# SIGNAL.net
KiCad netlist of a schematic drawn in Altium Designer
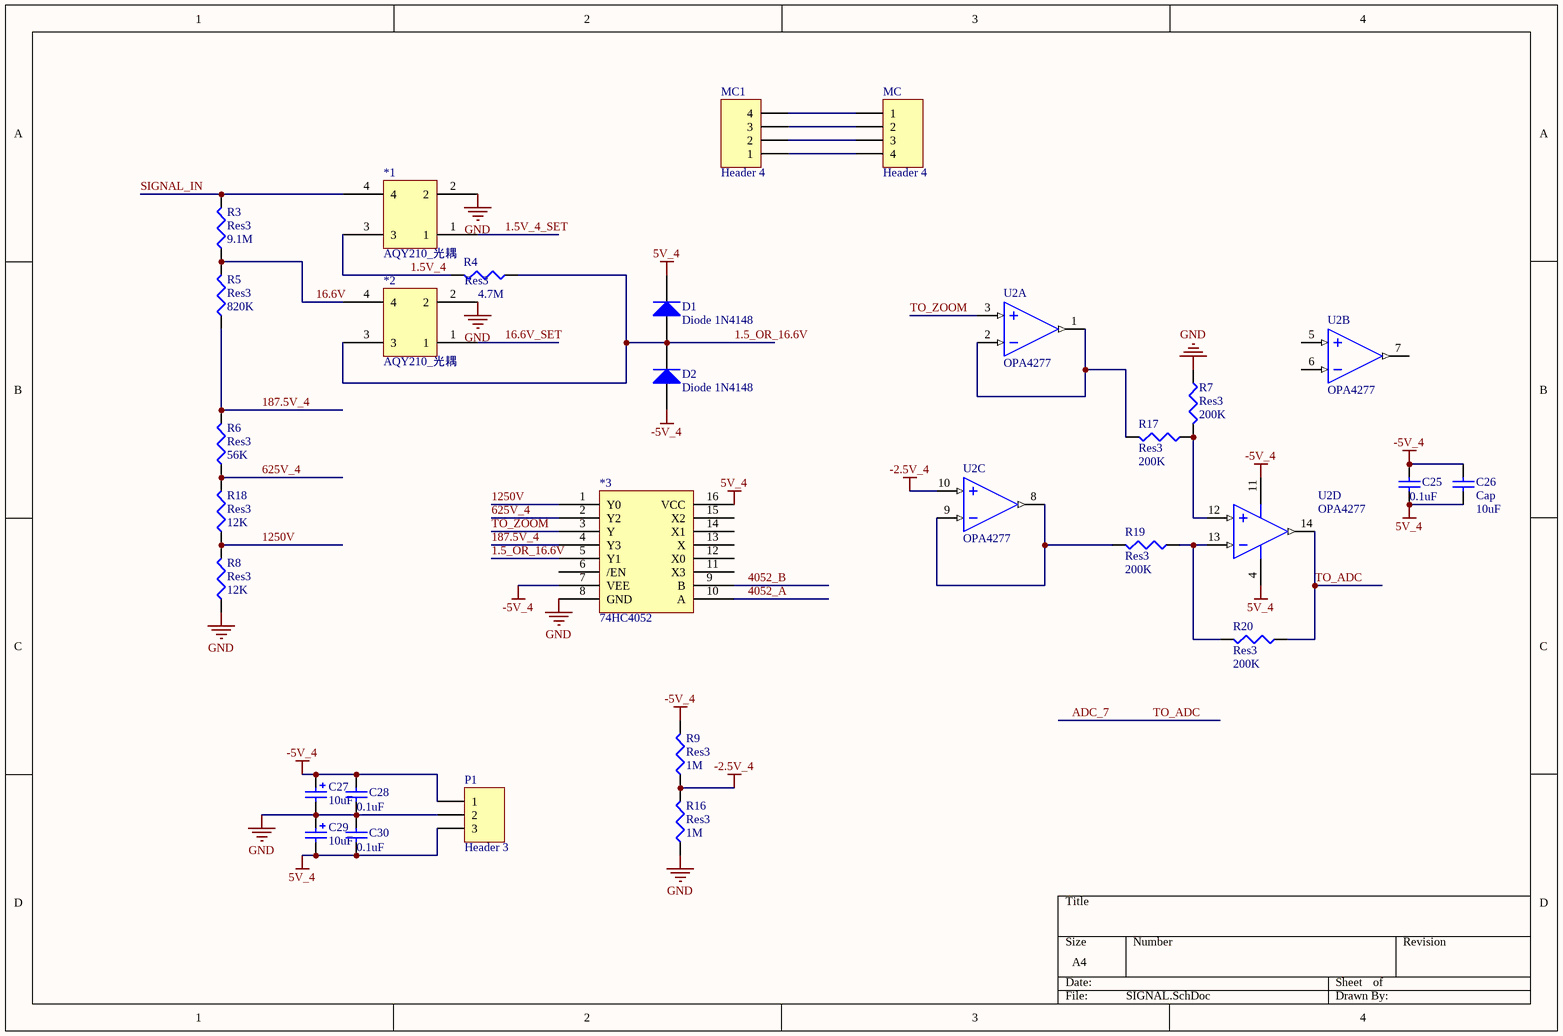
[diagram p0: SIGNAL.SchDoc]

(export (version "E")
  (design (tool "Eeschema 10.0.6"))
  (components
    (comp (ref "*1")
      (value "AQY210_光耦")
      (footprint "SOT254P605X218-4N")
      (description "AQY210")
      (libsource (lib "SINGAL") (part "AQY210_光耦"))
    )
    (comp (ref "*2")
      (value "AQY210_光耦")
      (footprint "SOT254P605X218-4N")
      (description "AQY210")
      (libsource (lib "SINGAL") (part "AQY210_光耦"))
    )
    (comp (ref "*3") (value "74HC4052") (footprint "SOP-16") (libsource (lib "SIGNAL") (part "74HC4052")))
    (comp (ref "C25")
      (value "0.1uF")
      (footprint "c0805")
      (description "Capacitor")
      (fields (field (name "Comment") "Cap") (field (name "PUBLISHER") "Altium Limited"))
      (libsource (lib "Miscellaneous Devices") (part "Cap"))
    )
    (comp (ref "C26")
      (value "Cap")
      (footprint "c0805")
      (description "Capacitor")
      (fields (field (name "ALTIUM_VALUE") "10uF") (field (name "PUBLISHER") "Altium Limited"))
      (libsource (lib "Miscellaneous Devices") (part "Cap"))
    )
    (comp (ref "C27")
      (value "10uF")
      (footprint "C1206")
      (description "Polarized Capacitor (Axial)")
      (fields (field (name "Comment") "Cap Pol2") (field (name "PUBLISHER") "Altium Limited"))
      (libsource (lib "Miscellaneous Devices") (part "Cap Pol2"))
    )
    (comp (ref "C28")
      (value "0.1uF")
      (footprint "0805")
      (description "Capacitor")
      (fields (field (name "Comment") "Cap") (field (name "PUBLISHER") "Altium Limited"))
      (libsource (lib "Miscellaneous Devices") (part "Cap"))
    )
    (comp (ref "C29")
      (value "10uF")
      (footprint "C1206")
      (description "Polarized Capacitor (Axial)")
      (fields (field (name "Comment") "Cap Pol2") (field (name "PUBLISHER") "Altium Limited"))
      (libsource (lib "Miscellaneous Devices") (part "Cap Pol2"))
    )
    (comp (ref "C30")
      (value "0.1uF")
      (footprint "0805")
      (description "Capacitor")
      (fields (field (name "Comment") "Cap") (field (name "PUBLISHER") "Altium Limited"))
      (libsource (lib "Miscellaneous Devices") (part "Cap"))
    )
    (comp (ref "D1")
      (value "Diode 1N4148")
      (footprint "0805")
      (description "1 Amp General Purpose Rectifier")
      (fields (field (name "PUBLISHER") "Altium Limited"))
      (libsource (lib "Miscellaneous Devices") (part "Diode 1N4002"))
    )
    (comp (ref "D2")
      (value "Diode 1N4148")
      (footprint "0805")
      (description "1 Amp General Purpose Rectifier")
      (fields (field (name "PUBLISHER") "Altium Limited"))
      (libsource (lib "Miscellaneous Devices") (part "Diode 1N4002"))
    )
    (comp (ref "MC")
      (value "Header 4")
      (footprint "耳机插座:PCBComponent_1")
      (description "Header, 4-Pin")
      (fields (field (name "PUBLISHER") "Altium Limited"))
      (libsource (lib "") (part "Header 4_1"))
    )
    (comp (ref "MC1")
      (value "Header 4")
      (footprint "HDR1X4")
      (description "Header, 4-Pin")
      (fields (field (name "PUBLISHER") "Altium Limited"))
      (libsource (lib "Miscellaneous Connectors") (part "Header 4"))
    )
    (comp (ref "P1")
      (value "Header 3")
      (footprint "HDR1X3")
      (description "Header, 3-Pin")
      (fields (field (name "PUBLISHER") "Altium Limited"))
      (libsource (lib "Miscellaneous Connectors") (part "Header 3"))
    )
    (comp (ref "R3")
      (value "Res3")
      (footprint "0805")
      (description "Resistor")
      (fields (field (name "ALTIUM_VALUE") "9.1M") (field (name "PUBLISHER") "Altium Limited"))
      (libsource (lib "Miscellaneous Devices") (part "Res3"))
    )
    (comp (ref "R4")
      (value "Res3")
      (footprint "0805")
      (description "Resistor")
      (fields (field (name "ALTIUM_VALUE") "4.7M") (field (name "PUBLISHER") "Altium Limited"))
      (libsource (lib "Miscellaneous Devices") (part "Res3"))
    )
    (comp (ref "R5")
      (value "Res3")
      (footprint "0805")
      (description "Resistor")
      (fields (field (name "ALTIUM_VALUE") "820K") (field (name "PUBLISHER") "Altium Limited"))
      (libsource (lib "Miscellaneous Devices") (part "Res3"))
    )
    (comp (ref "R6")
      (value "Res3")
      (footprint "0805")
      (description "Resistor")
      (fields (field (name "ALTIUM_VALUE") "56K") (field (name "PUBLISHER") "Altium Limited"))
      (libsource (lib "Miscellaneous Devices") (part "Res3"))
    )
    (comp (ref "R7")
      (value "Res3")
      (footprint "0805")
      (description "Resistor")
      (fields (field (name "ALTIUM_VALUE") "200K") (field (name "PUBLISHER") "Altium Limited"))
      (libsource (lib "Miscellaneous Devices") (part "Res3"))
    )
    (comp (ref "R8")
      (value "Res3")
      (footprint "0805")
      (description "Resistor")
      (fields (field (name "ALTIUM_VALUE") "12K") (field (name "PUBLISHER") "Altium Limited"))
      (libsource (lib "Miscellaneous Devices") (part "Res3"))
    )
    (comp (ref "R9")
      (value "Res3")
      (footprint "0805")
      (description "Resistor")
      (fields (field (name "ALTIUM_VALUE") "1M") (field (name "PUBLISHER") "Altium Limited"))
      (libsource (lib "Miscellaneous Devices") (part "Res3"))
    )
    (comp (ref "R16")
      (value "Res3")
      (footprint "0805")
      (description "Resistor")
      (fields (field (name "ALTIUM_VALUE") "1M") (field (name "PUBLISHER") "Altium Limited"))
      (libsource (lib "Miscellaneous Devices") (part "Res3"))
    )
    (comp (ref "R17")
      (value "Res3")
      (footprint "0805")
      (description "Resistor")
      (fields (field (name "ALTIUM_VALUE") "200K") (field (name "PUBLISHER") "Altium Limited"))
      (libsource (lib "Miscellaneous Devices") (part "Res3"))
    )
    (comp (ref "R18")
      (value "Res3")
      (footprint "0805")
      (description "Resistor")
      (fields (field (name "ALTIUM_VALUE") "12K") (field (name "PUBLISHER") "Altium Limited"))
      (libsource (lib "Miscellaneous Devices") (part "Res3"))
    )
    (comp (ref "R19")
      (value "Res3")
      (footprint "0805")
      (description "Resistor")
      (fields (field (name "ALTIUM_VALUE") "200K") (field (name "PUBLISHER") "Altium Limited"))
      (libsource (lib "Miscellaneous Devices") (part "Res3"))
    )
    (comp (ref "R20")
      (value "Res3")
      (footprint "0805")
      (description "Resistor")
      (fields (field (name "ALTIUM_VALUE") "200K") (field (name "PUBLISHER") "Altium Limited"))
      (libsource (lib "Miscellaneous Devices") (part "Res3"))
    )
    (comp (ref "U2")
      (value "OPA4277")
      (footprint "SO-14")
      (description "High Precision Operational Amplifiers")
      (libsource (lib "SIGNAL") (part "OPA4277"))
    )
  )
  (nets
    (net (code "1") (name "-2.5V_4") (class "Default")
      (node (ref "R16") (pin "2") (pinfunction "2_2") (pintype "passive"))
      (node (ref "R9") (pin "1") (pinfunction "1_1") (pintype "passive"))
      (node (ref "U2") (pin "10") (pinfunction "IN+_10") (pintype "input"))
    )
    (net (code "2") (name "-5V_4") (class "Default")
      (node (ref "*3") (pin "7") (pinfunction "VEE_7") (pintype "passive"))
      (node (ref "C25") (pin "2") (pinfunction "2_2") (pintype "passive"))
      (node (ref "C26") (pin "2") (pinfunction "2_2") (pintype "passive"))
      (node (ref "C27") (pin "1") (pinfunction "1_1") (pintype "passive"))
      (node (ref "C28") (pin "2") (pinfunction "2_2") (pintype "passive"))
      (node (ref "D2") (pin "1") (pinfunction "A_1") (pintype "passive"))
      (node (ref "P1") (pin "1") (pinfunction "1_1") (pintype "passive"))
      (node (ref "R9") (pin "2") (pinfunction "2_2") (pintype "passive"))
      (node (ref "U2") (pin "11") (pinfunction "V-_11") (pintype "power_in"))
    )
    (net (code "3") (name "/1.5V_4") (class "Default")
      (node (ref "*1") (pin "3") (pinfunction "3_3") (pintype "passive"))
      (node (ref "R4") (pin "2") (pinfunction "2_2") (pintype "passive"))
    )
    (net (code "4") (name "/1.5V_4_SET") (class "Default")
      (node (ref "*1") (pin "1") (pinfunction "1_1") (pintype "passive"))
    )
    (net (code "5") (name "/1.5_OR_16.6V") (class "Default")
      (node (ref "*2") (pin "3") (pinfunction "3_3") (pintype "passive"))
      (node (ref "*3") (pin "5") (pinfunction "Y1_5") (pintype "passive"))
      (node (ref "D1") (pin "1") (pinfunction "A_1") (pintype "passive"))
      (node (ref "D2") (pin "2") (pinfunction "K_2") (pintype "passive"))
      (node (ref "R4") (pin "1") (pinfunction "1_1") (pintype "passive"))
    )
    (net (code "6") (name "/16.6V") (class "Default")
      (node (ref "*2") (pin "4") (pinfunction "4_4") (pintype "passive"))
      (node (ref "R3") (pin "1") (pinfunction "1_1") (pintype "passive"))
      (node (ref "R5") (pin "2") (pinfunction "2_2") (pintype "passive"))
    )
    (net (code "7") (name "/16.6V_SET") (class "Default")
      (node (ref "*2") (pin "1") (pinfunction "1_1") (pintype "passive"))
    )
    (net (code "8") (name "/187.5V_4") (class "Default")
      (node (ref "*3") (pin "4") (pinfunction "Y3_4") (pintype "passive"))
      (node (ref "R5") (pin "1") (pinfunction "1_1") (pintype "passive"))
      (node (ref "R6") (pin "2") (pinfunction "2_2") (pintype "passive"))
    )
    (net (code "9") (name "/625V_4") (class "Default")
      (node (ref "*3") (pin "2") (pinfunction "Y2_2") (pintype "passive"))
      (node (ref "R18") (pin "2") (pinfunction "2_2") (pintype "passive"))
      (node (ref "R6") (pin "1") (pinfunction "1_1") (pintype "passive"))
    )
    (net (code "10") (name "/1250V") (class "Default")
      (node (ref "*3") (pin "1") (pinfunction "Y0_1") (pintype "passive"))
      (node (ref "R18") (pin "1") (pinfunction "1_1") (pintype "passive"))
      (node (ref "R8") (pin "2") (pinfunction "2_2") (pintype "passive"))
    )
    (net (code "11") (name "/4052_A") (class "Default")
      (node (ref "*3") (pin "10") (pinfunction "A_10") (pintype "passive"))
    )
    (net (code "12") (name "/4052_B") (class "Default")
      (node (ref "*3") (pin "9") (pinfunction "B_9") (pintype "passive"))
    )
    (net (code "13") (name "/ADC_7") (class "Default")
      (node (ref "R20") (pin "1") (pinfunction "1_1") (pintype "passive"))
      (node (ref "U2") (pin "14") (pinfunction "OUT_14") (pintype "output"))
    )
    (net (code "14") (name "/SIGNAL_IN") (class "Default")
      (node (ref "*1") (pin "4") (pinfunction "4_4") (pintype "passive"))
      (node (ref "R3") (pin "2") (pinfunction "2_2") (pintype "passive"))
    )
    (net (code "15") (name "/TO_ZOOM") (class "Default")
      (node (ref "*3") (pin "3") (pinfunction "Y_3") (pintype "passive"))
      (node (ref "U2") (pin "3") (pinfunction "IN+_3") (pintype "input"))
    )
    (net (code "16") (name "5V_4") (class "Default")
      (node (ref "*3") (pin "16") (pinfunction "VCC_16") (pintype "passive"))
      (node (ref "C25") (pin "1") (pinfunction "1_1") (pintype "passive"))
      (node (ref "C26") (pin "1") (pinfunction "1_1") (pintype "passive"))
      (node (ref "C29") (pin "2") (pinfunction "2_2") (pintype "passive"))
      (node (ref "C30") (pin "1") (pinfunction "1_1") (pintype "passive"))
      (node (ref "D1") (pin "2") (pinfunction "K_2") (pintype "passive"))
      (node (ref "P1") (pin "3") (pinfunction "3_3") (pintype "passive"))
      (node (ref "U2") (pin "4") (pinfunction "V+_4") (pintype "power_in"))
    )
    (net (code "17") (name "GND") (class "Default")
      (node (ref "*1") (pin "2") (pinfunction "2_2") (pintype "passive"))
      (node (ref "*2") (pin "2") (pinfunction "2_2") (pintype "passive"))
      (node (ref "*3") (pin "8") (pinfunction "GND_8") (pintype "passive"))
      (node (ref "C27") (pin "2") (pinfunction "2_2") (pintype "passive"))
      (node (ref "C28") (pin "1") (pinfunction "1_1") (pintype "passive"))
      (node (ref "C29") (pin "1") (pinfunction "1_1") (pintype "passive"))
      (node (ref "C30") (pin "2") (pinfunction "2_2") (pintype "passive"))
      (node (ref "P1") (pin "2") (pinfunction "2_2") (pintype "passive"))
      (node (ref "R16") (pin "1") (pinfunction "1_1") (pintype "passive"))
      (node (ref "R7") (pin "1") (pinfunction "1_1") (pintype "passive"))
      (node (ref "R8") (pin "1") (pinfunction "1_1") (pintype "passive"))
    )
    (net (code "18") (name "Net-(MC-Pad1)") (class "Default")
      (node (ref "MC") (pin "1") (pinfunction "1_1") (pintype "passive"))
      (node (ref "MC1") (pin "4") (pinfunction "4_4") (pintype "passive"))
    )
    (net (code "19") (name "Net-(MC-Pad2)") (class "Default")
      (node (ref "MC") (pin "2") (pinfunction "2_2") (pintype "passive"))
      (node (ref "MC1") (pin "3") (pinfunction "3_3") (pintype "passive"))
    )
    (net (code "20") (name "Net-(MC-Pad3)") (class "Default")
      (node (ref "MC") (pin "3") (pinfunction "3_3") (pintype "passive"))
      (node (ref "MC1") (pin "2") (pinfunction "2_2") (pintype "passive"))
    )
    (net (code "21") (name "Net-(MC-Pad4)") (class "Default")
      (node (ref "MC") (pin "4") (pinfunction "4_4") (pintype "passive"))
      (node (ref "MC1") (pin "1") (pinfunction "1_1") (pintype "passive"))
    )
    (net (code "22") (name "Net-(U2A-IN-)") (class "Default")
      (node (ref "R17") (pin "2") (pinfunction "2_2") (pintype "passive"))
      (node (ref "U2") (pin "1") (pinfunction "OUT_1") (pintype "output"))
      (node (ref "U2") (pin "2") (pinfunction "IN-_2") (pintype "input"))
    )
    (net (code "23") (name "Net-(U2C-IN-)") (class "Default")
      (node (ref "R19") (pin "2") (pinfunction "2_2") (pintype "passive"))
      (node (ref "U2") (pin "8") (pinfunction "OUT_8") (pintype "output"))
      (node (ref "U2") (pin "9") (pinfunction "IN-_9") (pintype "input"))
    )
    (net (code "24") (name "Net-(U2D-IN+)") (class "Default")
      (node (ref "R17") (pin "1") (pinfunction "1_1") (pintype "passive"))
      (node (ref "R7") (pin "2") (pinfunction "2_2") (pintype "passive"))
      (node (ref "U2") (pin "12") (pinfunction "IN+_12") (pintype "input"))
    )
    (net (code "25") (name "Net-(U2D-IN-)") (class "Default")
      (node (ref "R19") (pin "1") (pinfunction "1_1") (pintype "passive"))
      (node (ref "R20") (pin "2") (pinfunction "2_2") (pintype "passive"))
      (node (ref "U2") (pin "13") (pinfunction "IN-_13") (pintype "input"))
    )
    (net (code "26") (name "unconnected-(*3-X-Pad13)") (class "Default")
      (node (ref "*3") (pin "13") (pinfunction "X_13") (pintype "passive"))
    )
    (net (code "27") (name "unconnected-(*3-X0-Pad12)") (class "Default")
      (node (ref "*3") (pin "12") (pinfunction "X0_12") (pintype "passive"))
    )
    (net (code "28") (name "unconnected-(*3-X1-Pad14)") (class "Default")
      (node (ref "*3") (pin "14") (pinfunction "X1_14") (pintype "passive"))
    )
    (net (code "29") (name "unconnected-(*3-X2-Pad15)") (class "Default")
      (node (ref "*3") (pin "15") (pinfunction "X2_15") (pintype "passive"))
    )
    (net (code "30") (name "unconnected-(*3-X3-Pad11)") (class "Default")
      (node (ref "*3") (pin "11") (pinfunction "X3_11") (pintype "passive"))
    )
    (net (code "31") (name "unconnected-(*3-{slash}EN-Pad6)") (class "Default")
      (node (ref "*3") (pin "6") (pinfunction "/EN_6") (pintype "passive"))
    )
    (net (code "32") (name "unconnected-(U2B-IN+-Pad5)") (class "Default")
      (node (ref "U2") (pin "5") (pinfunction "IN+_5") (pintype "input"))
    )
    (net (code "33") (name "unconnected-(U2B-IN--Pad6)") (class "Default")
      (node (ref "U2") (pin "6") (pinfunction "IN-_6") (pintype "input"))
    )
    (net (code "34") (name "unconnected-(U2B-OUT-Pad7)") (class "Default")
      (node (ref "U2") (pin "7") (pinfunction "OUT_7") (pintype "output"))
    )
  )
)
